# BLEbee-1_0_0.net
KiCad netlist of a schematic drawn in EAGLE
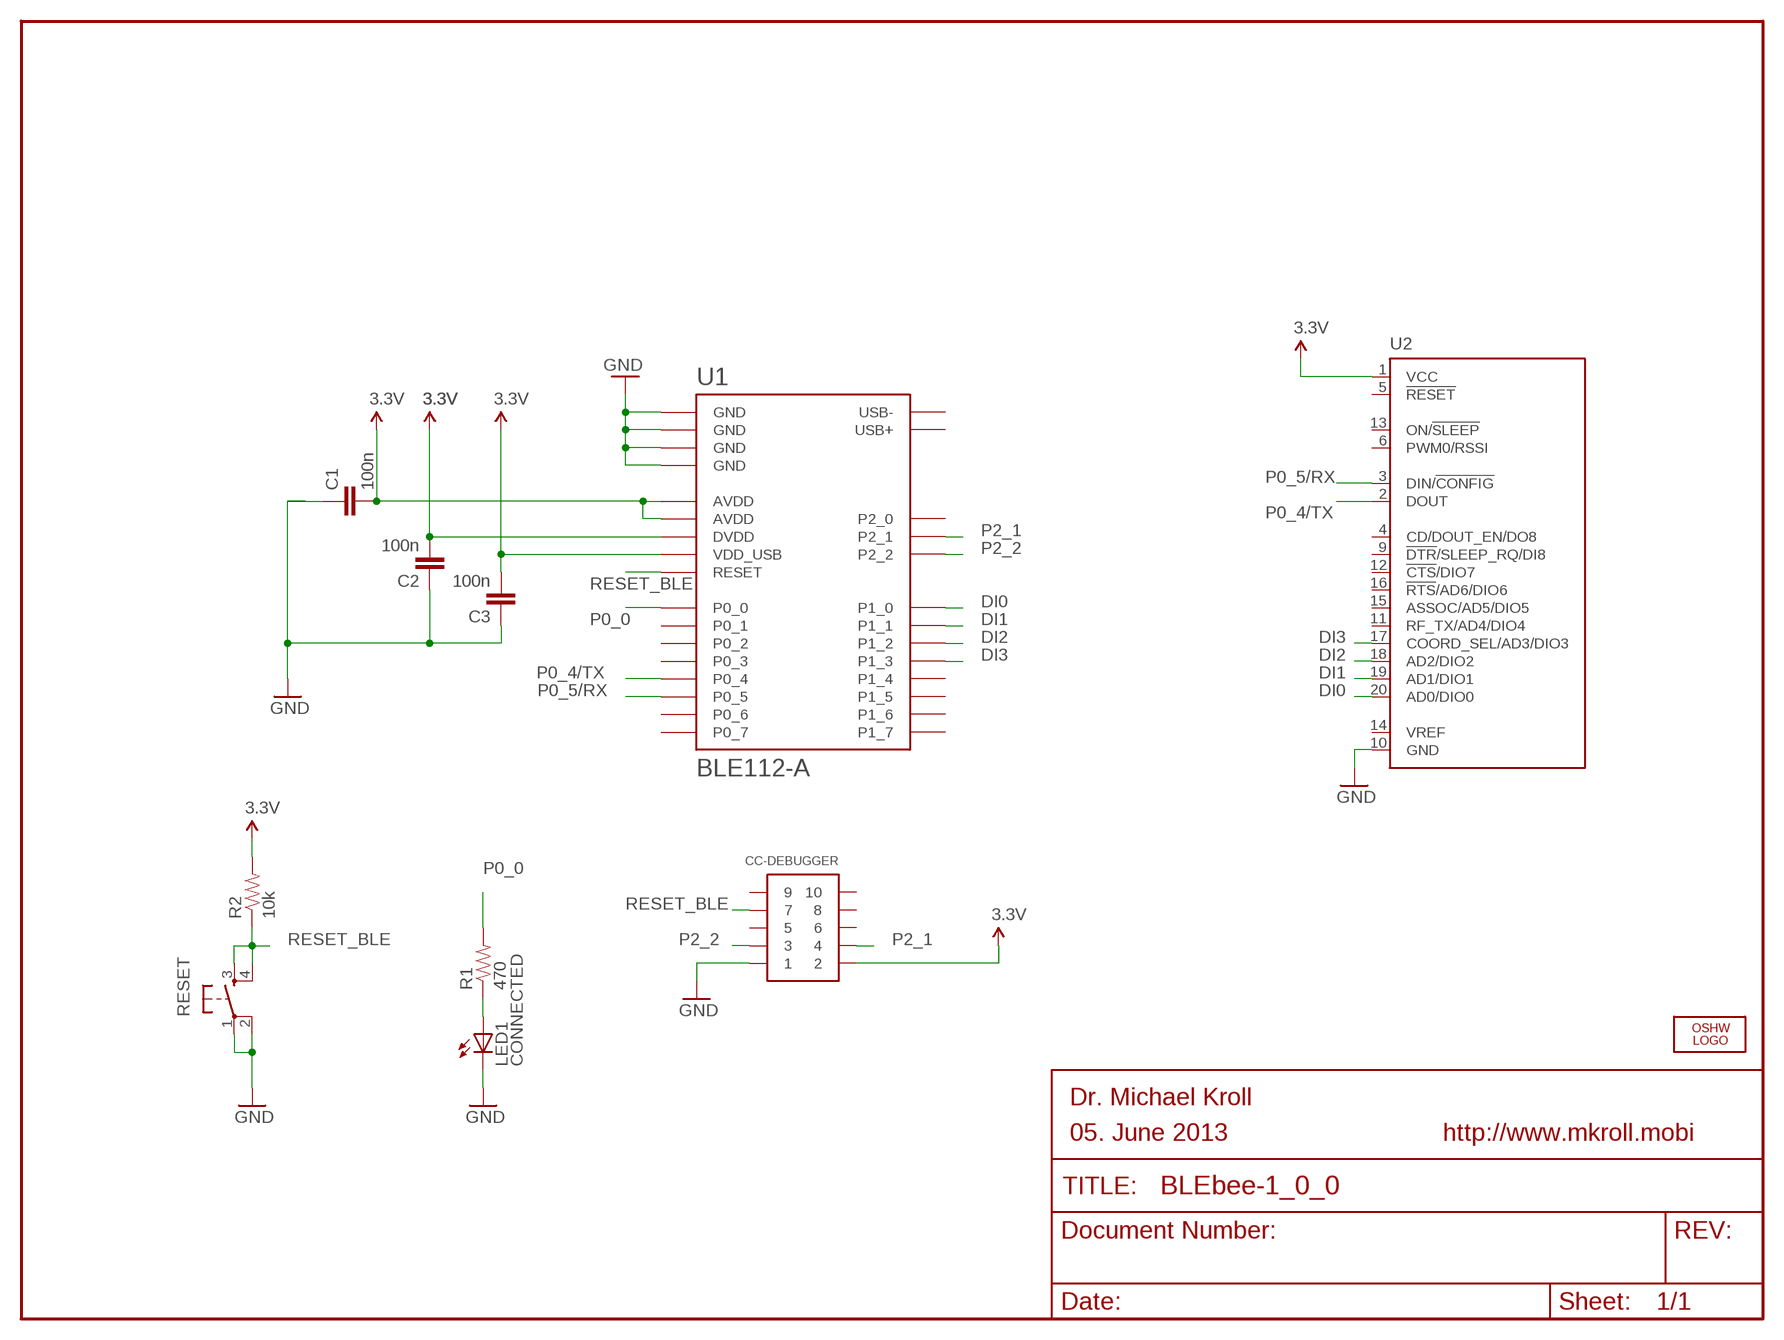
[diagram p0: schematic, sheet 1]

(export (version "E")
  (design (tool "Eeschema 10.0.6"))
  (components
    (comp (ref "C1")
      (value "100n")
      (footprint "eagle-import:0402-CAP")
      (libsource (lib "eagle-import") (part "CAP0402-CAP"))
    )
    (comp (ref "C2")
      (value "100n")
      (footprint "eagle-import:0402-CAP")
      (libsource (lib "eagle-import") (part "CAP0402-CAP"))
    )
    (comp (ref "C3")
      (value "100n")
      (footprint "eagle-import:0402-CAP")
      (libsource (lib "eagle-import") (part "CAP0402-CAP"))
    )
    (comp (ref "CC-DEBUGGER")
      (value "CONN_5-2-FTSH-V")
      (footprint "eagle-import:FTSH-105-DV")
      (libsource (lib "eagle-import") (part "CONN_5-2-FTSH-V"))
    )
    (comp (ref "LED1")
      (value "CONNECTED")
      (footprint "eagle-import:LED-0603")
      (libsource (lib "eagle-import") (part "LED0603"))
    )
    (comp (ref "LOGO1")
      (value "LOGO-OSHW-6MILX0100-NT")
      (footprint "eagle-import:OSHW_6X100_NOTEXT")
      (libsource (lib "eagle-import") (part "LOGO-OSHW-6MILX0100-NT"))
    )
    (comp (ref "R1")
      (value "470")
      (footprint "eagle-import:0402-RES")
      (libsource (lib "eagle-import") (part "RESISTOR0402-RES"))
    )
    (comp (ref "R2")
      (value "10k")
      (footprint "eagle-import:0402-RES")
      (libsource (lib "eagle-import") (part "RESISTOR0402-RES"))
    )
    (comp (ref "RESET")
      (value "TAC_SWITCHSMD")
      (footprint "eagle-import:TACTILE_SWITCH_SMD")
      (libsource (lib "eagle-import") (part "TAC_SWITCHSMD"))
    )
    (comp (ref "U1")
      (value "BLE112-A")
      (footprint "eagle-import:BLE112-A")
      (libsource (lib "eagle-import") (part "BLE112-A"))
    )
    (comp (ref "U2")
      (value "BEE-XBEE-DIP")
      (footprint "eagle-import:20P-DIP-2.0-W_-SILK")
      (libsource (lib "eagle-import") (part "BEE-XBEE-DIP"))
    )
  )
  (nets
    (net (code "1") (name "/DI0") (class "Default")
      (node (ref "U1") (pin "P1_0") (pinfunction "P1_0_P1_0") (pintype "bidirectional"))
      (node (ref "U2") (pin "20") (pinfunction "AD0/DIO0_20") (pintype "bidirectional"))
    )
    (net (code "2") (name "/DI1") (class "Default")
      (node (ref "U1") (pin "P1_1") (pinfunction "P1_1_P1_1") (pintype "bidirectional"))
      (node (ref "U2") (pin "19") (pinfunction "AD1/DIO1_19") (pintype "bidirectional"))
    )
    (net (code "3") (name "/DI2") (class "Default")
      (node (ref "U1") (pin "P1_2") (pinfunction "P1_2_P1_2") (pintype "bidirectional"))
      (node (ref "U2") (pin "18") (pinfunction "AD2/DIO2_18") (pintype "bidirectional"))
    )
    (net (code "4") (name "/DI3") (class "Default")
      (node (ref "U1") (pin "P1_3") (pinfunction "P1_3_P1_3") (pintype "bidirectional"))
      (node (ref "U2") (pin "17") (pinfunction "COORD_SEL/AD3/DIO3_17") (pintype "bidirectional"))
    )
    (net (code "5") (name "/P0_0") (class "Default")
      (node (ref "R1") (pin "2") (pinfunction "2_2") (pintype "passive"))
      (node (ref "U1") (pin "P0_0") (pinfunction "P0_0_P0_0") (pintype "bidirectional"))
    )
    (net (code "6") (name "/P0_4{slash}TX") (class "Default")
      (node (ref "U1") (pin "P0_4") (pinfunction "P0_4_P0_4") (pintype "bidirectional"))
      (node (ref "U2") (pin "2") (pinfunction "DOUT_2") (pintype "output"))
    )
    (net (code "7") (name "/P0_5{slash}RX") (class "Default")
      (node (ref "U1") (pin "P0_5") (pinfunction "P0_5_P0_5") (pintype "bidirectional"))
      (node (ref "U2") (pin "3") (pinfunction "DIN/~{CONFIG}_3") (pintype "input"))
    )
    (net (code "8") (name "/P2_1") (class "Default")
      (node (ref "CC-DEBUGGER") (pin "4") (pinfunction "4_4") (pintype "bidirectional"))
      (node (ref "U1") (pin "P2_1") (pinfunction "P2_1_P2_1") (pintype "bidirectional"))
    )
    (net (code "9") (name "/P2_2") (class "Default")
      (node (ref "CC-DEBUGGER") (pin "3") (pinfunction "3_3") (pintype "bidirectional"))
      (node (ref "U1") (pin "P2_2") (pinfunction "P2_2_P2_2") (pintype "bidirectional"))
    )
    (net (code "10") (name "/RESET_BLE") (class "Default")
      (node (ref "CC-DEBUGGER") (pin "7") (pinfunction "7_7") (pintype "bidirectional"))
      (node (ref "R2") (pin "1") (pinfunction "1_1") (pintype "passive"))
      (node (ref "RESET") (pin "3") (pinfunction "3_3") (pintype "passive"))
      (node (ref "RESET") (pin "4") (pinfunction "4_4") (pintype "passive"))
      (node (ref "U1") (pin "RESET") (pinfunction "RESET_RESET") (pintype "input"))
    )
    (net (code "11") (name "3.3V") (class "Default")
      (node (ref "C1") (pin "2") (pinfunction "2_2") (pintype "passive"))
      (node (ref "C2") (pin "2") (pinfunction "2_2") (pintype "passive"))
      (node (ref "C3") (pin "2") (pinfunction "2_2") (pintype "passive"))
      (node (ref "CC-DEBUGGER") (pin "2") (pinfunction "2_2") (pintype "bidirectional"))
      (node (ref "R2") (pin "2") (pinfunction "2_2") (pintype "passive"))
      (node (ref "U1") (pin "AVDD1") (pinfunction "AVDD_AVDD1") (pintype "power_in"))
      (node (ref "U1") (pin "AVDD2") (pinfunction "AVDD_AVDD2") (pintype "power_in"))
      (node (ref "U1") (pin "DVDD") (pinfunction "DVDD_DVDD") (pintype "power_in"))
      (node (ref "U1") (pin "VDD_USB") (pinfunction "VDD_USB_VDD_USB") (pintype "power_in"))
      (node (ref "U2") (pin "1") (pinfunction "VCC_1") (pintype "power_in"))
    )
    (net (code "12") (name "GND") (class "Default")
      (node (ref "C1") (pin "1") (pinfunction "1_1") (pintype "passive"))
      (node (ref "C2") (pin "1") (pinfunction "1_1") (pintype "passive"))
      (node (ref "C3") (pin "1") (pinfunction "1_1") (pintype "passive"))
      (node (ref "CC-DEBUGGER") (pin "1") (pinfunction "1_1") (pintype "bidirectional"))
      (node (ref "LED1") (pin "C") (pinfunction "C_C") (pintype "passive"))
      (node (ref "RESET") (pin "1") (pinfunction "1_1") (pintype "passive"))
      (node (ref "RESET") (pin "2") (pinfunction "2_2") (pintype "passive"))
      (node (ref "U1") (pin "GND1") (pinfunction "GND_GND1") (pintype "power_in"))
      (node (ref "U1") (pin "GND2") (pinfunction "GND_GND2") (pintype "power_in"))
      (node (ref "U1") (pin "GND3") (pinfunction "GND_GND3") (pintype "power_in"))
      (node (ref "U1") (pin "GND4") (pinfunction "GND_GND4") (pintype "power_in"))
      (node (ref "U2") (pin "10") (pinfunction "GND_10") (pintype "bidirectional"))
    )
    (net (code "13") (name "Net-(LED1-PadA)") (class "Default")
      (node (ref "LED1") (pin "A") (pinfunction "A_A") (pintype "passive"))
      (node (ref "R1") (pin "1") (pinfunction "1_1") (pintype "passive"))
    )
    (net (code "14") (name "unconnected-(CC-DEBUGGER-Pad5)") (class "Default")
      (node (ref "CC-DEBUGGER") (pin "5") (pinfunction "5_5") (pintype "bidirectional"))
    )
    (net (code "15") (name "unconnected-(CC-DEBUGGER-Pad6)") (class "Default")
      (node (ref "CC-DEBUGGER") (pin "6") (pinfunction "6_6") (pintype "bidirectional"))
    )
    (net (code "16") (name "unconnected-(CC-DEBUGGER-Pad8)") (class "Default")
      (node (ref "CC-DEBUGGER") (pin "8") (pinfunction "8_8") (pintype "bidirectional"))
    )
    (net (code "17") (name "unconnected-(CC-DEBUGGER-Pad9)") (class "Default")
      (node (ref "CC-DEBUGGER") (pin "9") (pinfunction "9_9") (pintype "bidirectional"))
    )
    (net (code "18") (name "unconnected-(CC-DEBUGGER-Pad10)") (class "Default")
      (node (ref "CC-DEBUGGER") (pin "10") (pinfunction "10_10") (pintype "bidirectional"))
    )
    (net (code "19") (name "unconnected-(U1-PadP0_1)") (class "Default")
      (node (ref "U1") (pin "P0_1") (pinfunction "P0_1_P0_1") (pintype "bidirectional"))
    )
    (net (code "20") (name "unconnected-(U1-PadP0_2)") (class "Default")
      (node (ref "U1") (pin "P0_2") (pinfunction "P0_2_P0_2") (pintype "bidirectional"))
    )
    (net (code "21") (name "unconnected-(U1-PadP0_3)") (class "Default")
      (node (ref "U1") (pin "P0_3") (pinfunction "P0_3_P0_3") (pintype "bidirectional"))
    )
    (net (code "22") (name "unconnected-(U1-PadP0_6)") (class "Default")
      (node (ref "U1") (pin "P0_6") (pinfunction "P0_6_P0_6") (pintype "bidirectional"))
    )
    (net (code "23") (name "unconnected-(U1-PadP0_7)") (class "Default")
      (node (ref "U1") (pin "P0_7") (pinfunction "P0_7_P0_7") (pintype "bidirectional"))
    )
    (net (code "24") (name "unconnected-(U1-PadP1_4)") (class "Default")
      (node (ref "U1") (pin "P1_4") (pinfunction "P1_4_P1_4") (pintype "bidirectional"))
    )
    (net (code "25") (name "unconnected-(U1-PadP1_5)") (class "Default")
      (node (ref "U1") (pin "P1_5") (pinfunction "P1_5_P1_5") (pintype "bidirectional"))
    )
    (net (code "26") (name "unconnected-(U1-PadP1_6)") (class "Default")
      (node (ref "U1") (pin "P1_6") (pinfunction "P1_6_P1_6") (pintype "bidirectional"))
    )
    (net (code "27") (name "unconnected-(U1-PadP1_7)") (class "Default")
      (node (ref "U1") (pin "P1_7") (pinfunction "P1_7_P1_7") (pintype "bidirectional"))
    )
    (net (code "28") (name "unconnected-(U1-PadP2_0)") (class "Default")
      (node (ref "U1") (pin "P2_0") (pinfunction "P2_0_P2_0") (pintype "bidirectional"))
    )
    (net (code "29") (name "unconnected-(U1-PadUSB+)") (class "Default")
      (node (ref "U1") (pin "USB+") (pinfunction "USB+_USB+") (pintype "bidirectional"))
    )
    (net (code "30") (name "unconnected-(U1-PadUSB-)") (class "Default")
      (node (ref "U1") (pin "USB-") (pinfunction "USB-_USB-") (pintype "bidirectional"))
    )
    (net (code "31") (name "unconnected-(U2-ASSOC{slash}AD5{slash}DIO5-Pad15)") (class "Default")
      (node (ref "U2") (pin "15") (pinfunction "ASSOC/AD5/DIO5_15") (pintype "bidirectional"))
    )
    (net (code "32") (name "unconnected-(U2-CD{slash}DOUT_EN{slash}DO8-Pad4)") (class "Default")
      (node (ref "U2") (pin "4") (pinfunction "CD/DOUT_EN/DO8_4") (pintype "output"))
    )
    (net (code "33") (name "unconnected-(U2-ON{slash}~{SLEEP}-Pad13)") (class "Default")
      (node (ref "U2") (pin "13") (pinfunction "ON/~{SLEEP}_13") (pintype "output"))
    )
    (net (code "34") (name "unconnected-(U2-PWM0{slash}RSSI-Pad6)") (class "Default")
      (node (ref "U2") (pin "6") (pinfunction "PWM0/RSSI_6") (pintype "output"))
    )
    (net (code "35") (name "unconnected-(U2-RF_TX{slash}AD4{slash}DIO4-Pad11)") (class "Default")
      (node (ref "U2") (pin "11") (pinfunction "RF_TX/AD4/DIO4_11") (pintype "bidirectional"))
    )
    (net (code "36") (name "unconnected-(U2-VREF-Pad14)") (class "Default")
      (node (ref "U2") (pin "14") (pinfunction "VREF_14") (pintype "input"))
    )
    (net (code "37") (name "unconnected-(U2-~{CTS}{slash}DIO7-Pad12)") (class "Default")
      (node (ref "U2") (pin "12") (pinfunction "~{CTS}/DIO7_12") (pintype "bidirectional"))
    )
    (net (code "38") (name "unconnected-(U2-~{DTR}{slash}SLEEP_RQ{slash}DI8-Pad9)") (class "Default")
      (node (ref "U2") (pin "9") (pinfunction "~{DTR}/SLEEP_RQ/DI8_9") (pintype "bidirectional"))
    )
    (net (code "39") (name "unconnected-(U2-~{RESET}-Pad5)") (class "Default")
      (node (ref "U2") (pin "5") (pinfunction "~{RESET}_5") (pintype "input"))
    )
    (net (code "40") (name "unconnected-(U2-~{RTS}{slash}AD6{slash}DIO6-Pad16)") (class "Default")
      (node (ref "U2") (pin "16") (pinfunction "~{RTS}/AD6/DIO6_16") (pintype "bidirectional"))
    )
  )
)
